# USB_SPI.net
KiCad netlist of a schematic drawn in Altium Designer
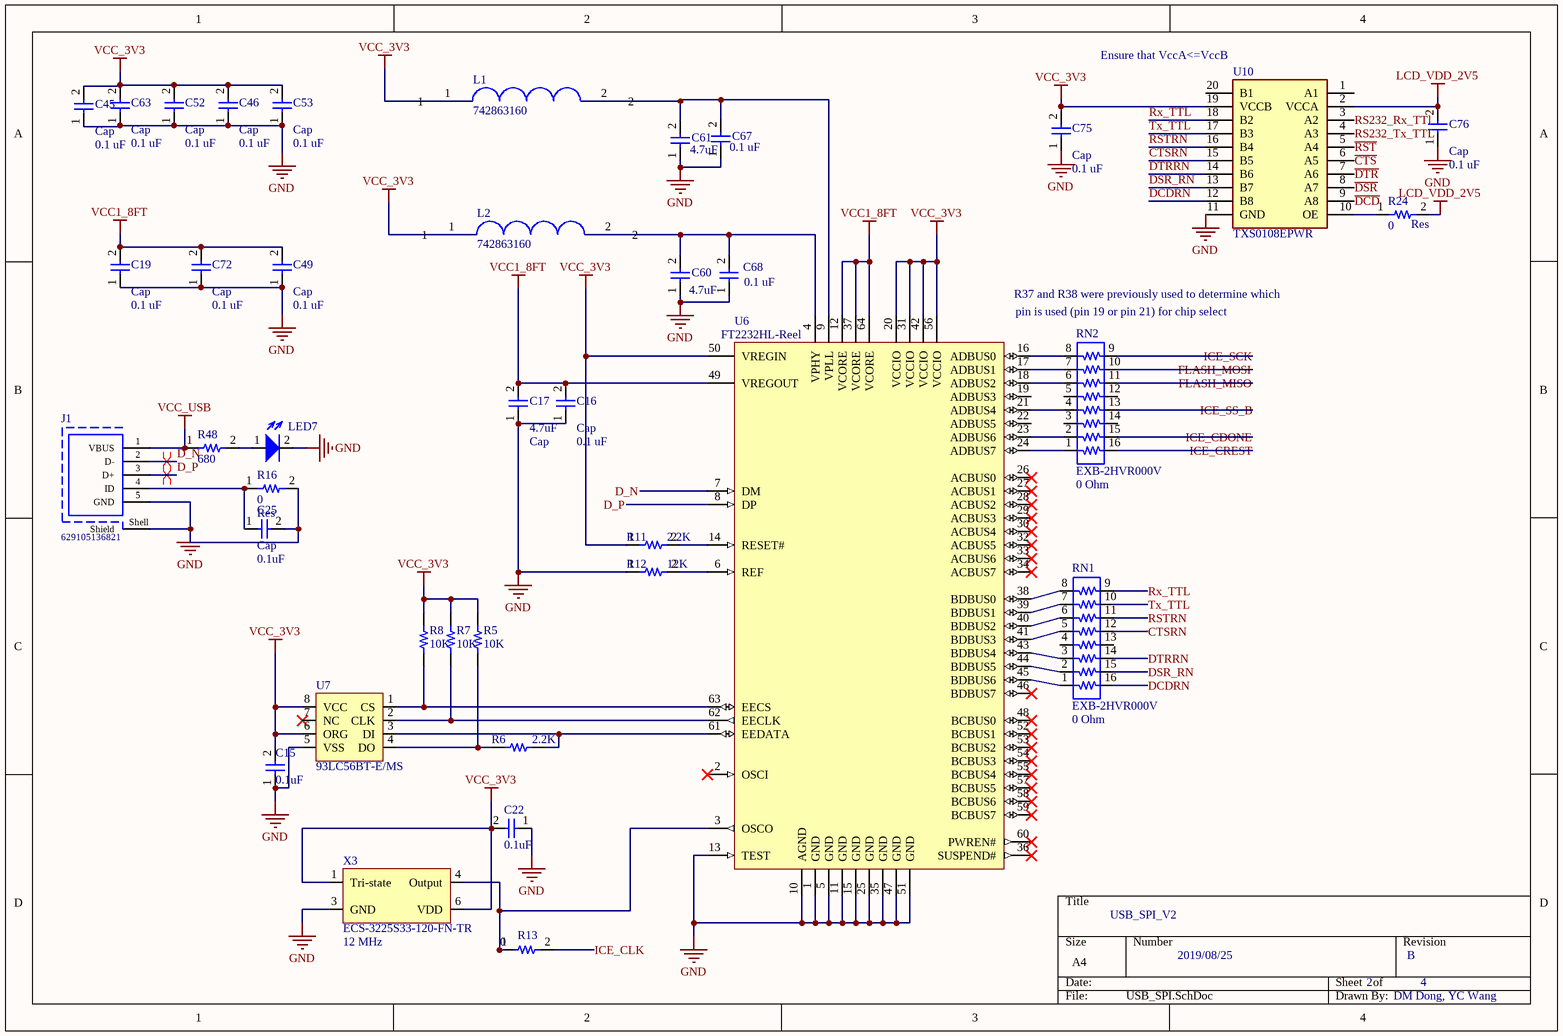
[diagram p0: USB_SPI.SchDoc]

(export (version "E")
  (design (tool "Eeschema 10.0.6"))
  (components
    (comp (ref "C15")
      (value "0.1uF")
      (footprint "Cap_0.1uF")
      (description "Multilayer Ceramic Capacitors MLCC - SMD/SMT 0.1uF 10% 50V AEC-Q200")
      (fields (field (name "Comment") "AC0603KRX7R9BB104") (field (name "CREATED BY") "Daoming Dong"))
      (libsource (lib "USB_FPGA_SLM_v1") (part "Cap_0.1uF"))
    )
    (comp (ref "C16")
      (value "0.1 uF")
      (footprint "Cap_0.1uF_0402")
      (description "Multilayer Ceramic Capacitors MLCC - SMD/SMT 100nF 10V X5R 10%")
      (fields
        (field (name "COMPONENT NAME") "Cap")
        (field (name "Comment") "CC0402KPX5R6BB104")
        (field (name "CREATED BY") "Daoming Dong")
      )
      (libsource (lib "USB_FPGA_SLM_v1") (part "CAP_0.1uF_0402"))
    )
    (comp (ref "C17")
      (value "4.7uF")
      (footprint "CAP_4.7uF_0402")
      (description "Multilayer Ceramic Capacitors MLCC - SMD/SMT 0402 6.3V 4.7uF X5R 10% T: 0.5mm")
      (fields
        (field (name "COMPONENT NAME") "Cap")
        (field (name "Comment") "C1005X5R0J475K050BC")
        (field (name "CREATED BY") "Daoming Dong")
      )
      (libsource (lib "USB_FPGA_SLM_v1") (part "Cap_4.7uF_0402"))
    )
    (comp (ref "C19")
      (value "0.1 uF")
      (footprint "Cap_0.1uF_0402")
      (description "Multilayer Ceramic Capacitors MLCC - SMD/SMT 100nF 10V X5R 10%")
      (fields
        (field (name "COMPONENT NAME") "Cap")
        (field (name "Comment") "CC0402KPX5R6BB104")
        (field (name "CREATED BY") "Daoming Dong")
      )
      (libsource (lib "USB_FPGA_SLM_v1") (part "CAP_0.1uF_0402"))
    )
    (comp (ref "C22")
      (value "0.1uF")
      (footprint "Cap_0.1uF")
      (description "Multilayer Ceramic Capacitors MLCC - SMD/SMT 0.1uF 10% 50V AEC-Q200")
      (fields (field (name "Comment") "AC0603KRX7R9BB104") (field (name "CREATED BY") "Daoming Dong"))
      (libsource (lib "USB_FPGA_SLM_v1") (part "Cap_0.1uF"))
    )
    (comp (ref "C25")
      (value "0.1uF")
      (footprint "Cap_0.1uF")
      (description "Multilayer Ceramic Capacitors MLCC - SMD/SMT 0.1uF 10% 50V AEC-Q200")
      (fields
        (field (name "COMPONENT NAME") "Cap")
        (field (name "Comment") "AC0603KRX7R9BB104")
        (field (name "CREATED BY") "Daoming Dong")
      )
      (libsource (lib "USB_FPGA_SLM_v1") (part "Cap_0.1uF"))
    )
    (comp (ref "C45")
      (value "0.1 uF")
      (footprint "Cap_0.1uF_0402")
      (description "Multilayer Ceramic Capacitors MLCC - SMD/SMT 100nF 10V X5R 10%")
      (fields
        (field (name "COMPONENT NAME") "Cap")
        (field (name "Comment") "CC0402KPX5R6BB104")
        (field (name "CREATED BY") "Daoming Dong")
      )
      (libsource (lib "USB_FPGA_SLM_v1") (part "CAP_0.1uF_0402"))
    )
    (comp (ref "C46")
      (value "0.1 uF")
      (footprint "Cap_0.1uF_0402")
      (description "Multilayer Ceramic Capacitors MLCC - SMD/SMT 100nF 10V X5R 10%")
      (fields
        (field (name "COMPONENT NAME") "Cap")
        (field (name "Comment") "CC0402KPX5R6BB104")
        (field (name "CREATED BY") "Daoming Dong")
      )
      (libsource (lib "USB_FPGA_SLM_v1") (part "CAP_0.1uF_0402"))
    )
    (comp (ref "C49")
      (value "0.1 uF")
      (footprint "Cap_0.1uF_0402")
      (description "Multilayer Ceramic Capacitors MLCC - SMD/SMT 100nF 10V X5R 10%")
      (fields
        (field (name "COMPONENT NAME") "Cap")
        (field (name "Comment") "CC0402KPX5R6BB104")
        (field (name "CREATED BY") "Daoming Dong")
      )
      (libsource (lib "USB_FPGA_SLM_v1") (part "CAP_0.1uF_0402"))
    )
    (comp (ref "C52")
      (value "0.1 uF")
      (footprint "Cap_0.1uF_0402")
      (description "Multilayer Ceramic Capacitors MLCC - SMD/SMT 100nF 10V X5R 10%")
      (fields
        (field (name "COMPONENT NAME") "Cap")
        (field (name "Comment") "CC0402KPX5R6BB104")
        (field (name "CREATED BY") "Daoming Dong")
      )
      (libsource (lib "USB_FPGA_SLM_v1") (part "CAP_0.1uF_0402"))
    )
    (comp (ref "C53")
      (value "0.1 uF")
      (footprint "Cap_0.1uF_0402")
      (description "Multilayer Ceramic Capacitors MLCC - SMD/SMT 100nF 10V X5R 10%")
      (fields
        (field (name "COMPONENT NAME") "Cap")
        (field (name "Comment") "CC0402KPX5R6BB104")
        (field (name "CREATED BY") "Daoming Dong")
      )
      (libsource (lib "USB_FPGA_SLM_v1") (part "CAP_0.1uF_0402"))
    )
    (comp (ref "C60")
      (value "4.7uF")
      (footprint "CAP_4.7uF_0402")
      (description "Multilayer Ceramic Capacitors MLCC - SMD/SMT 0402 6.3V 4.7uF X5R 10% T: 0.5mm")
      (fields (field (name "Comment") "C1005X5R0J475K050BC") (field (name "CREATED BY") "Daoming Dong"))
      (libsource (lib "USB_FPGA_SLM_v1") (part "Cap_4.7uF_0402"))
    )
    (comp (ref "C61")
      (value "4.7uF")
      (footprint "CAP_4.7uF_0402")
      (description "Multilayer Ceramic Capacitors MLCC - SMD/SMT 0402 6.3V 4.7uF X5R 10% T: 0.5mm")
      (fields (field (name "Comment") "C1005X5R0J475K050BC") (field (name "CREATED BY") "Daoming Dong"))
      (libsource (lib "USB_FPGA_SLM_v1") (part "Cap_4.7uF_0402"))
    )
    (comp (ref "C63")
      (value "0.1 uF")
      (footprint "Cap_0.1uF_0402")
      (description "Multilayer Ceramic Capacitors MLCC - SMD/SMT 100nF 10V X5R 10%")
      (fields
        (field (name "COMPONENT NAME") "Cap")
        (field (name "Comment") "CC0402KPX5R6BB104")
        (field (name "CREATED BY") "Daoming Dong")
      )
      (libsource (lib "USB_FPGA_SLM_v1") (part "CAP_0.1uF_0402"))
    )
    (comp (ref "C67")
      (value "0.1 uF")
      (footprint "Cap_0.1uF_0402")
      (description "Multilayer Ceramic Capacitors MLCC - SMD/SMT 100nF 10V X5R 10%")
      (fields (field (name "Comment") "CC0402KPX5R6BB104") (field (name "CREATED BY") "Daoming Dong"))
      (libsource (lib "USB_FPGA_SLM_v1") (part "CAP_0.1uF_0402"))
    )
    (comp (ref "C68")
      (value "0.1 uF")
      (footprint "Cap_0.1uF_0402")
      (description "Multilayer Ceramic Capacitors MLCC - SMD/SMT 100nF 10V X5R 10%")
      (fields (field (name "Comment") "CC0402KPX5R6BB104") (field (name "CREATED BY") "Daoming Dong"))
      (libsource (lib "USB_FPGA_SLM_v1") (part "CAP_0.1uF_0402"))
    )
    (comp (ref "C72")
      (value "0.1 uF")
      (footprint "Cap_0.1uF_0402")
      (description "Multilayer Ceramic Capacitors MLCC - SMD/SMT 100nF 10V X5R 10%")
      (fields
        (field (name "COMPONENT NAME") "Cap")
        (field (name "Comment") "CC0402KPX5R6BB104")
        (field (name "CREATED BY") "Daoming Dong")
      )
      (libsource (lib "USB_FPGA_SLM_v1") (part "CAP_0.1uF_0402"))
    )
    (comp (ref "C75")
      (value "0.1 uF")
      (footprint "Cap_0.1uF_0402")
      (description "Multilayer Ceramic Capacitors MLCC - SMD/SMT 100nF 10V X5R 10%")
      (fields
        (field (name "COMPONENT NAME") "Cap")
        (field (name "Comment") "CC0402KPX5R6BB104")
        (field (name "CREATED BY") "Daoming Dong")
      )
      (libsource (lib "USB_FPGA_SLM_v1") (part "CAP_0.1uF_0402"))
    )
    (comp (ref "C76")
      (value "0.1 uF")
      (footprint "Cap_0.1uF_0402")
      (description "Multilayer Ceramic Capacitors MLCC - SMD/SMT 100nF 10V X5R 10%")
      (fields
        (field (name "COMPONENT NAME") "Cap")
        (field (name "Comment") "CC0402KPX5R6BB104")
        (field (name "CREATED BY") "Daoming Dong")
      )
      (libsource (lib "USB_FPGA_SLM_v1") (part "CAP_0.1uF_0402"))
    )
    (comp (ref "J1")
      (value "629105136821")
      (footprint "629105136821")
      (description "Micro USB 2.0 Type B Receptacle WR-COM, Horizontal, SMT, with Pads and Pegs")
      (fields (field (name "PUBLISHER") "Wurth Elektronik"))
      (libsource (lib "Altium_WR-COM_USB-Connectors (rev18d)") (part "629105136821"))
    )
    (comp (ref "L1")
      (value "742863160")
      (footprint "FerriteBeads")
      (description "Ferrite Bead, 0603 [1608 Metric], 600 ohm, 500 mA, WE-CBF HF Series, 0.35 ohm, ± 25%")
      (fields (field (name "CREATED BY") "Youchao Wang"))
      (libsource (lib "USB_FPGA_SLM_v1") (part "Ferrite Bead"))
    )
    (comp (ref "L2")
      (value "742863160")
      (footprint "FerriteBeads")
      (description "Ferrite Bead, 0603 [1608 Metric], 600 ohm, 500 mA, WE-CBF HF Series, 0.35 ohm, ± 25%")
      (fields (field (name "CREATED BY") "Youchao Wang"))
      (libsource (lib "USB_FPGA_SLM_v1") (part "Ferrite Bead"))
    )
    (comp (ref "LED7")
      (value "TLMS1000-GS08")
      (footprint "LED_RED")
      (description "Standard LEDs - SMD RED")
      (fields (field (name "CREATED BY") "Daoming Dong"))
      (libsource (lib "USB_FPGA_SLM_v1") (part "LED_RED"))
    )
    (comp (ref "R5")
      (value "10K")
      (footprint "RES_10K")
      (description "Thin Film Resistors - SMD 10K ohm 0.05% 50 ppm High-Precision")
      (fields (field (name "Comment") "RT0603WRE0710KL") (field (name "CREATED BY") "Daoming Dong"))
      (libsource (lib "USB_FPGA_SLM_v1") (part "Res_10K"))
    )
    (comp (ref "R6")
      (value "2.2K")
      (footprint "RES_2.2K")
      (description "Thick Film Resistors - SMD 1/10Watt 2.2Kohms 5% Commercial Use")
      (fields (field (name "Comment") "CRCW06032K20JNEAC") (field (name "CREATED BY") "Daoming Dong"))
      (libsource (lib "USB_FPGA_SLM_v1") (part "Res_2.2K"))
    )
    (comp (ref "R7")
      (value "10K")
      (footprint "RES_10K")
      (description "Thin Film Resistors - SMD 10K ohm 0.05% 50 ppm High-Precision")
      (fields (field (name "Comment") "RT0603WRE0710KL") (field (name "CREATED BY") "Daoming Dong"))
      (libsource (lib "USB_FPGA_SLM_v1") (part "Res_10K"))
    )
    (comp (ref "R8")
      (value "10K")
      (footprint "RES_10K")
      (description "Thin Film Resistors - SMD 10K ohm 0.05% 50 ppm High-Precision")
      (fields (field (name "Comment") "RT0603WRE0710KL") (field (name "CREATED BY") "Daoming Dong"))
      (libsource (lib "USB_FPGA_SLM_v1") (part "Res_10K"))
    )
    (comp (ref "R11")
      (value "2.2K")
      (footprint "RES_2.2K")
      (description "Thick Film Resistors - SMD 1/10Watt 2.2Kohms 5% Commercial Use")
      (fields (field (name "Comment") "CRCW06032K20JNEAC") (field (name "CREATED BY") "Daoming Dong"))
      (libsource (lib "") (part "Res_2.2K_1"))
    )
    (comp (ref "R12")
      (value "12K")
      (footprint "RES_12K")
      (description "Thick Film Resistors - SMD 12K ohm 1% 1/10W AEC-Q200")
      (fields (field (name "Comment") "AC0603FR-1012KL") (field (name "CREATED BY") "Daoming Dong"))
      (libsource (lib "USB_FPGA_SLM_v1") (part "Res_12K"))
    )
    (comp (ref "R13")
      (value "0")
      (footprint "RES_0")
      (description "Thick Film Resistors - SMD 1/10Watt 0ohms Commercial Use")
      (fields (field (name "Comment") "CRCW06030000Z0EAC") (field (name "CREATED BY") "Daoming Dong"))
      (libsource (lib "USB_FPGA_SLM_v1") (part "Res_0"))
    )
    (comp (ref "R16")
      (value "0")
      (footprint "RES_0")
      (description "Thick Film Resistors - SMD 1/10Watt 0ohms Commercial Use")
      (fields
        (field (name "COMPONENT NAME") "Res")
        (field (name "Comment") "CRCW06030000Z0EAC")
        (field (name "CREATED BY") "Daoming Dong")
      )
      (libsource (lib "USB_FPGA_SLM_v1") (part "Res_0"))
    )
    (comp (ref "R24")
      (value "0")
      (footprint "RES_0")
      (description "Thick Film Resistors - SMD 1/10Watt 0ohms Commercial Use")
      (fields
        (field (name "COMPONENT NAME") "Res")
        (field (name "Comment") "CRCW06030000Z0EAC")
        (field (name "CREATED BY") "Daoming Dong")
      )
      (libsource (lib "USB_FPGA_SLM_v1") (part "Res_0"))
    )
    (comp (ref "R48")
      (value "680")
      (footprint "RES_680")
      (description "Thin Film Resistors - SMD 680 ohm 1% 50 ppm Thin Film")
      (fields (field (name "Comment") "RT0603FRE13680RL") (field (name "CREATED BY") "Daoming Dong"))
      (libsource (lib "USB_FPGA_SLM_v1") (part "Res_680"))
    )
    (comp (ref "RN1")
      (value "EXB-2HVR000V")
      (footprint "ResArray_0")
      (description "Resistor Networks & Arrays 0402 Zero ohm Jumper Convex Term AEC-Q200")
      (fields (field (name "ALTIUM_VALUE") "0 Ohm") (field (name "CREATED BY") "Daoming Dong"))
      (libsource (lib "USB_FPGA_SLM_v1") (part "ResArray_0"))
    )
    (comp (ref "RN2")
      (value "EXB-2HVR000V")
      (footprint "ResArray_0")
      (description "Resistor Networks & Arrays 0402 Zero ohm Jumper Convex Term AEC-Q200")
      (fields (field (name "ALTIUM_VALUE") "0 Ohm") (field (name "CREATED BY") "Daoming Dong"))
      (libsource (lib "USB_FPGA_SLM_v1") (part "ResArray_0"))
    )
    (comp (ref "U6")
      (value "FT2232HL-Reel")
      (footprint "LQFP-64_N")
      (description "Dual High Speed USB To Multipurpose UART/FIFO IC, 64-pin LQFP, Tape and Reel")
      (fields (field (name "MANUFACTURER") "FTDI"))
      (libsource (lib "FTDI FT Series") (part "FT2232HL-Reel"))
    )
    (comp (ref "U7")
      (value "93LC56BT-E/MS")
      (footprint "EEPROM")
      (description "EEPROM 128x16 for FT2232")
      (fields (field (name "CREATED BY") "Daoming Dong"))
      (libsource (lib "USB_FPGA_SLM_v1") (part "EEPROM"))
    )
    (comp (ref "U10")
      (value "TXS0108EPWR")
      (footprint "SOP65P640X120-20N")
      (description "Integrated Circuit")
      (fields (field (name "MOUSER PART NUMBER") "595-TXS0108EPWR"))
      (libsource (lib "USB_FPGA_SLM_v1") (part "Level_Shfter_8bits"))
    )
    (comp (ref "X3")
      (value "ECS-3225S33-120-FN-TR")
      (footprint "12MHzOscillator")
      (description "Standard Clock Oscillators 12MHz 3.3V 10ppm -40C +85C")
      (fields (field (name "ALTIUM_VALUE") "12 MHz"))
      (libsource (lib "USB_FPGA_SLM_v1") (part "12MHzOscillator"))
    )
  )
  (nets
    (net (code "1") (name "/CTSRN") (class "Default")
      (node (ref "RN1") (pin "12") (pinfunction "12_12") (pintype "passive"))
      (node (ref "U10") (pin "15") (pinfunction "B5_15") (pintype "passive"))
    )
    (net (code "2") (name "/DCDRN") (class "Default")
      (node (ref "RN1") (pin "16") (pinfunction "16_16") (pintype "passive"))
      (node (ref "U10") (pin "12") (pinfunction "B8_12") (pintype "passive"))
    )
    (net (code "3") (name "/DSR_RN") (class "Default")
      (node (ref "RN1") (pin "15") (pinfunction "15_15") (pintype "passive"))
      (node (ref "U10") (pin "13") (pinfunction "B7_13") (pintype "passive"))
    )
    (net (code "4") (name "/DTRRN") (class "Default")
      (node (ref "RN1") (pin "14") (pinfunction "14_14") (pintype "passive"))
      (node (ref "U10") (pin "14") (pinfunction "B6_14") (pintype "passive"))
    )
    (net (code "5") (name "/D_N") (class "Default")
      (node (ref "J1") (pin "2") (pinfunction "D-_2") (pintype "passive"))
      (node (ref "U6") (pin "7") (pinfunction "DM_7") (pintype "input"))
    )
    (net (code "6") (name "/D_P") (class "Default")
      (node (ref "J1") (pin "3") (pinfunction "D+_3") (pintype "passive"))
      (node (ref "U6") (pin "8") (pinfunction "DP_8") (pintype "input"))
    )
    (net (code "7") (name "/FLASH_MISO") (class "Default")
      (node (ref "RN2") (pin "11") (pinfunction "11_11") (pintype "passive"))
    )
    (net (code "8") (name "/FLASH_MOSI") (class "Default")
      (node (ref "RN2") (pin "10") (pinfunction "10_10") (pintype "passive"))
    )
    (net (code "9") (name "/ICE_CDONE") (class "Default")
      (node (ref "RN2") (pin "15") (pinfunction "15_15") (pintype "passive"))
    )
    (net (code "10") (name "/ICE_CLK") (class "Default")
      (node (ref "R13") (pin "2") (pinfunction "2_2") (pintype "passive"))
    )
    (net (code "11") (name "/ICE_CREST") (class "Default")
      (node (ref "RN2") (pin "16") (pinfunction "16_16") (pintype "passive"))
    )
    (net (code "12") (name "/ICE_SCK") (class "Default")
      (node (ref "RN2") (pin "9") (pinfunction "9_9") (pintype "passive"))
    )
    (net (code "13") (name "/ICE_SS_B") (class "Default")
      (node (ref "RN2") (pin "13") (pinfunction "13_13") (pintype "passive"))
    )
    (net (code "14") (name "/RS232_Rx_TTl") (class "Default")
      (node (ref "U10") (pin "3") (pinfunction "A2_3") (pintype "passive"))
    )
    (net (code "15") (name "/RS232_Tx_TTL") (class "Default")
      (node (ref "U10") (pin "4") (pinfunction "A3_4") (pintype "passive"))
    )
    (net (code "16") (name "/RSTRN") (class "Default")
      (node (ref "RN1") (pin "11") (pinfunction "11_11") (pintype "passive"))
      (node (ref "U10") (pin "16") (pinfunction "B4_16") (pintype "passive"))
    )
    (net (code "17") (name "/Rx_TTL") (class "Default")
      (node (ref "RN1") (pin "9") (pinfunction "9_9") (pintype "passive"))
      (node (ref "U10") (pin "18") (pinfunction "B2_18") (pintype "passive"))
    )
    (net (code "18") (name "/Tx_TTL") (class "Default")
      (node (ref "RN1") (pin "10") (pinfunction "10_10") (pintype "passive"))
      (node (ref "U10") (pin "17") (pinfunction "B3_17") (pintype "passive"))
    )
    (net (code "19") (name "/~{CTS}") (class "Default")
      (node (ref "U10") (pin "6") (pinfunction "A5_6") (pintype "passive"))
    )
    (net (code "20") (name "/~{DCD}") (class "Default")
      (node (ref "U10") (pin "9") (pinfunction "A8_9") (pintype "passive"))
    )
    (net (code "21") (name "/~{DSR}") (class "Default")
      (node (ref "U10") (pin "8") (pinfunction "A7_8") (pintype "passive"))
    )
    (net (code "22") (name "/~{DTR}") (class "Default")
      (node (ref "U10") (pin "7") (pinfunction "A6_7") (pintype "passive"))
    )
    (net (code "23") (name "/~{RST}") (class "Default")
      (node (ref "U10") (pin "5") (pinfunction "A4_5") (pintype "passive"))
    )
    (net (code "24") (name "GND") (class "Default")
      (node (ref "C15") (pin "1") (pinfunction "1_1") (pintype "passive"))
      (node (ref "C16") (pin "1") (pinfunction "1_1") (pintype "passive"))
      (node (ref "C17") (pin "1") (pinfunction "1_1") (pintype "passive"))
      (node (ref "C19") (pin "1") (pinfunction "1_1") (pintype "passive"))
      (node (ref "C22") (pin "1") (pinfunction "1_1") (pintype "passive"))
      (node (ref "C25") (pin "2") (pinfunction "2_2") (pintype "passive"))
      (node (ref "C45") (pin "1") (pinfunction "1_1") (pintype "passive"))
      (node (ref "C46") (pin "1") (pinfunction "1_1") (pintype "passive"))
      (node (ref "C49") (pin "1") (pinfunction "1_1") (pintype "passive"))
      (node (ref "C52") (pin "1") (pinfunction "1_1") (pintype "passive"))
      (node (ref "C53") (pin "1") (pinfunction "1_1") (pintype "passive"))
      (node (ref "C60") (pin "1") (pinfunction "1_1") (pintype "passive"))
      (node (ref "C61") (pin "1") (pinfunction "1_1") (pintype "passive"))
      (node (ref "C63") (pin "1") (pinfunction "1_1") (pintype "passive"))
      (node (ref "C67") (pin "1") (pinfunction "1_1") (pintype "passive"))
      (node (ref "C68") (pin "1") (pinfunction "1_1") (pintype "passive"))
      (node (ref "C72") (pin "1") (pinfunction "1_1") (pintype "passive"))
      (node (ref "C75") (pin "1") (pinfunction "1_1") (pintype "passive"))
      (node (ref "C76") (pin "1") (pinfunction "1_1") (pintype "passive"))
      (node (ref "J1") (pin "5") (pinfunction "GND_5") (pintype "passive"))
      (node (ref "J1") (pin "Shell") (pinfunction "Shield_Shell") (pintype "passive"))
      (node (ref "LED7") (pin "2") (pinfunction "Cathode_2") (pintype "passive"))
      (node (ref "R12") (pin "1") (pinfunction "1_1") (pintype "passive"))
      (node (ref "R16") (pin "2") (pinfunction "2_2") (pintype "passive"))
      (node (ref "U10") (pin "11") (pinfunction "GND_11") (pintype "passive"))
      (node (ref "U6") (pin "1") (pinfunction "GND_1") (pintype "power_in"))
      (node (ref "U6") (pin "10") (pinfunction "AGND_10") (pintype "power_in"))
      (node (ref "U6") (pin "11") (pinfunction "GND_11") (pintype "power_in"))
      (node (ref "U6") (pin "13") (pinfunction "TEST_13") (pintype "input"))
      (node (ref "U6") (pin "15") (pinfunction "GND_15") (pintype "power_in"))
      (node (ref "U6") (pin "25") (pinfunction "GND_25") (pintype "power_in"))
      (node (ref "U6") (pin "35") (pinfunction "GND_35") (pintype "power_in"))
      (node (ref "U6") (pin "47") (pinfunction "GND_47") (pintype "power_in"))
      (node (ref "U6") (pin "5") (pinfunction "GND_5") (pintype "power_in"))
      (node (ref "U6") (pin "51") (pinfunction "GND_51") (pintype "power_in"))
      (node (ref "U7") (pin "5") (pinfunction "VSS_5") (pintype "passive"))
      (node (ref "X3") (pin "3") (pinfunction "GND_3") (pintype "passive"))
    )
    (net (code "25") (name "LCD_VDD_2V5") (class "Default")
      (node (ref "C76") (pin "2") (pinfunction "2_2") (pintype "passive"))
      (node (ref "R24") (pin "2") (pinfunction "2_2") (pintype "passive"))
      (node (ref "U10") (pin "2") (pinfunction "VCCA_2") (pintype "passive"))
    )
    (net (code "26") (name "Net-(J1-ID)") (class "Default")
      (node (ref "C25") (pin "1") (pinfunction "1_1") (pintype "passive"))
      (node (ref "J1") (pin "4") (pinfunction "ID_4") (pintype "passive"))
      (node (ref "R16") (pin "1") (pinfunction "1_1") (pintype "passive"))
    )
    (net (code "27") (name "Net-(LED7-Anode)") (class "Default")
      (node (ref "LED7") (pin "1") (pinfunction "Anode_1") (pintype "passive"))
      (node (ref "R48") (pin "2") (pinfunction "2_2") (pintype "passive"))
    )
    (net (code "28") (name "Net-(U6-ADBUS0)") (class "Default")
      (node (ref "RN2") (pin "8") (pinfunction "8_8") (pintype "passive"))
      (node (ref "U6") (pin "16") (pinfunction "ADBUS0_16") (pintype "bidirectional"))
    )
    (net (code "29") (name "Net-(U6-ADBUS1)") (class "Default")
      (node (ref "RN2") (pin "7") (pinfunction "7_7") (pintype "passive"))
      (node (ref "U6") (pin "17") (pinfunction "ADBUS1_17") (pintype "bidirectional"))
    )
    (net (code "30") (name "Net-(U6-ADBUS2)") (class "Default")
      (node (ref "RN2") (pin "6") (pinfunction "6_6") (pintype "passive"))
      (node (ref "U6") (pin "18") (pinfunction "ADBUS2_18") (pintype "bidirectional"))
    )
    (net (code "31") (name "Net-(U6-ADBUS4)") (class "Default")
      (node (ref "RN2") (pin "4") (pinfunction "4_4") (pintype "passive"))
      (node (ref "U6") (pin "21") (pinfunction "ADBUS4_21") (pintype "bidirectional"))
    )
    (net (code "32") (name "Net-(U6-ADBUS6)") (class "Default")
      (node (ref "RN2") (pin "2") (pinfunction "2_2") (pintype "passive"))
      (node (ref "U6") (pin "23") (pinfunction "ADBUS6_23") (pintype "bidirectional"))
    )
    (net (code "33") (name "Net-(U6-ADBUS7)") (class "Default")
      (node (ref "RN2") (pin "1") (pinfunction "1_1") (pintype "passive"))
      (node (ref "U6") (pin "24") (pinfunction "ADBUS7_24") (pintype "bidirectional"))
    )
    (net (code "34") (name "Net-(U6-BDBUS0)") (class "Default")
      (node (ref "RN1") (pin "8") (pinfunction "8_8") (pintype "passive"))
      (node (ref "U6") (pin "38") (pinfunction "BDBUS0_38") (pintype "bidirectional"))
    )
    (net (code "35") (name "Net-(U6-BDBUS1)") (class "Default")
      (node (ref "RN1") (pin "7") (pinfunction "7_7") (pintype "passive"))
      (node (ref "U6") (pin "39") (pinfunction "BDBUS1_39") (pintype "bidirectional"))
    )
    (net (code "36") (name "Net-(U6-BDBUS2)") (class "Default")
      (node (ref "RN1") (pin "6") (pinfunction "6_6") (pintype "passive"))
      (node (ref "U6") (pin "40") (pinfunction "BDBUS2_40") (pintype "bidirectional"))
    )
    (net (code "37") (name "Net-(U6-BDBUS3)") (class "Default")
      (node (ref "RN1") (pin "5") (pinfunction "5_5") (pintype "passive"))
      (node (ref "U6") (pin "41") (pinfunction "BDBUS3_41") (pintype "bidirectional"))
    )
    (net (code "38") (name "Net-(U6-BDBUS4)") (class "Default")
      (node (ref "RN1") (pin "3") (pinfunction "3_3") (pintype "passive"))
      (node (ref "U6") (pin "43") (pinfunction "BDBUS4_43") (pintype "bidirectional"))
    )
    (net (code "39") (name "Net-(U6-BDBUS5)") (class "Default")
      (node (ref "RN1") (pin "2") (pinfunction "2_2") (pintype "passive"))
      (node (ref "U6") (pin "44") (pinfunction "BDBUS5_44") (pintype "bidirectional"))
    )
    (net (code "40") (name "Net-(U6-BDBUS6)") (class "Default")
      (node (ref "RN1") (pin "1") (pinfunction "1_1") (pintype "passive"))
      (node (ref "U6") (pin "45") (pinfunction "BDBUS6_45") (pintype "bidirectional"))
    )
    (net (code "41") (name "Net-(U6-EECLK)") (class "Default")
      (node (ref "R7") (pin "1") (pinfunction "1_1") (pintype "passive"))
      (node (ref "U6") (pin "62") (pinfunction "EECLK_62") (pintype "output"))
      (node (ref "U7") (pin "2") (pinfunction "CLK_2") (pintype "passive"))
    )
    (net (code "42") (name "Net-(U6-EECS)") (class "Default")
      (node (ref "R8") (pin "1") (pinfunction "1_1") (pintype "passive"))
      (node (ref "U6") (pin "63") (pinfunction "EECS_63") (pintype "bidirectional"))
      (node (ref "U7") (pin "1") (pinfunction "CS_1") (pintype "passive"))
    )
    (net (code "43") (name "Net-(U6-EEDATA)") (class "Default")
      (node (ref "R6") (pin "2") (pinfunction "2_2") (pintype "passive"))
      (node (ref "U6") (pin "61") (pinfunction "EEDATA_61") (pintype "bidirectional"))
      (node (ref "U7") (pin "3") (pinfunction "DI_3") (pintype "passive"))
    )
    (net (code "44") (name "Net-(U6-OSCO)") (class "Default")
      (node (ref "R13") (pin "1") (pinfunction "1_1") (pintype "passive"))
      (node (ref "U6") (pin "3") (pinfunction "OSCO_3") (pintype "output"))
      (node (ref "X3") (pin "4") (pinfunction "Output_4") (pintype "passive"))
    )
    (net (code "45") (name "Net-(U6-REF)") (class "Default")
      (node (ref "R12") (pin "2") (pinfunction "2_2") (pintype "passive"))
      (node (ref "U6") (pin "6") (pinfunction "REF_6") (pintype "input"))
    )
    (net (code "46") (name "Net-(U6-RESET#)") (class "Default")
      (node (ref "R11") (pin "2") (pinfunction "2_2") (pintype "passive"))
      (node (ref "U6") (pin "14") (pinfunction "RESET#_14") (pintype "input"))
    )
    (net (code "47") (name "Net-(U6-VPHY)") (class "Default")
      (node (ref "C60") (pin "2") (pinfunction "2_2") (pintype "passive"))
      (node (ref "C68") (pin "2") (pinfunction "2_2") (pintype "passive"))
      (node (ref "L2") (pin "2") (pinfunction "2_2") (pintype "passive"))
      (node (ref "U6") (pin "4") (pinfunction "VPHY_4") (pintype "power_in"))
    )
    (net (code "48") (name "Net-(U6-VPLL)") (class "Default")
      (node (ref "C61") (pin "2") (pinfunction "2_2") (pintype "passive"))
      (node (ref "C67") (pin "2") (pinfunction "2_2") (pintype "passive"))
      (node (ref "L1") (pin "2") (pinfunction "2_2") (pintype "passive"))
      (node (ref "U6") (pin "9") (pinfunction "VPLL_9") (pintype "power_in"))
    )
    (net (code "49") (name "Net-(U7-DO)") (class "Default")
      (node (ref "R5") (pin "1") (pinfunction "1_1") (pintype "passive"))
      (node (ref "R6") (pin "1") (pinfunction "1_1") (pintype "passive"))
      (node (ref "U7") (pin "4") (pinfunction "DO_4") (pintype "passive"))
    )
    (net (code "50") (name "Net-(U10-OE)") (class "Default")
      (node (ref "R24") (pin "1") (pinfunction "1_1") (pintype "passive"))
      (node (ref "U10") (pin "10") (pinfunction "OE_10") (pintype "passive"))
    )
    (net (code "51") (name "VCC1_8FT") (class "Default")
      (node (ref "C16") (pin "2") (pinfunction "2_2") (pintype "passive"))
      (node (ref "C17") (pin "2") (pinfunction "2_2") (pintype "passive"))
      (node (ref "C19") (pin "2") (pinfunction "2_2") (pintype "passive"))
      (node (ref "C49") (pin "2") (pinfunction "2_2") (pintype "passive"))
      (node (ref "C72") (pin "2") (pinfunction "2_2") (pintype "passive"))
      (node (ref "U6") (pin "12") (pinfunction "VCORE_12") (pintype "power_in"))
      (node (ref "U6") (pin "37") (pinfunction "VCORE_37") (pintype "power_in"))
      (node (ref "U6") (pin "49") (pinfunction "VREGOUT_49") (pintype "power_in"))
      (node (ref "U6") (pin "64") (pinfunction "VCORE_64") (pintype "power_in"))
    )
    (net (code "52") (name "VCC_3V3") (class "Default")
      (node (ref "C15") (pin "2") (pinfunction "2_2") (pintype "passive"))
      (node (ref "C22") (pin "2") (pinfunction "2_2") (pintype "passive"))
      (node (ref "C45") (pin "2") (pinfunction "2_2") (pintype "passive"))
      (node (ref "C46") (pin "2") (pinfunction "2_2") (pintype "passive"))
      (node (ref "C52") (pin "2") (pinfunction "2_2") (pintype "passive"))
      (node (ref "C53") (pin "2") (pinfunction "2_2") (pintype "passive"))
      (node (ref "C63") (pin "2") (pinfunction "2_2") (pintype "passive"))
      (node (ref "C75") (pin "2") (pinfunction "2_2") (pintype "passive"))
      (node (ref "L1") (pin "1") (pinfunction "1_1") (pintype "passive"))
      (node (ref "L2") (pin "1") (pinfunction "1_1") (pintype "passive"))
      (node (ref "R11") (pin "1") (pinfunction "1_1") (pintype "passive"))
      (node (ref "R5") (pin "2") (pinfunction "2_2") (pintype "passive"))
      (node (ref "R7") (pin "2") (pinfunction "2_2") (pintype "passive"))
      (node (ref "R8") (pin "2") (pinfunction "2_2") (pintype "passive"))
      (node (ref "U10") (pin "19") (pinfunction "VCCB_19") (pintype "passive"))
      (node (ref "U6") (pin "20") (pinfunction "VCCIO_20") (pintype "power_in"))
      (node (ref "U6") (pin "31") (pinfunction "VCCIO_31") (pintype "power_in"))
      (node (ref "U6") (pin "42") (pinfunction "VCCIO_42") (pintype "power_in"))
      (node (ref "U6") (pin "50") (pinfunction "VREGIN_50") (pintype "power_in"))
      (node (ref "U6") (pin "56") (pinfunction "VCCIO_56") (pintype "power_in"))
      (node (ref "U7") (pin "6") (pinfunction "ORG_6") (pintype "passive"))
      (node (ref "U7") (pin "8") (pinfunction "VCC_8") (pintype "passive"))
      (node (ref "X3") (pin "1") (pinfunction "Tri-state_1") (pintype "passive"))
      (node (ref "X3") (pin "6") (pinfunction "VDD_6") (pintype "passive"))
    )
    (net (code "53") (name "VCC_USB") (class "Default")
      (node (ref "J1") (pin "1") (pinfunction "VBUS_1") (pintype "passive"))
      (node (ref "R48") (pin "1") (pinfunction "1_1") (pintype "passive"))
    )
    (net (code "54") (name "unconnected-(RN1-Pad4)") (class "Default")
      (node (ref "RN1") (pin "4") (pinfunction "4_4") (pintype "passive"))
    )
    (net (code "55") (name "unconnected-(RN1-Pad13)") (class "Default")
      (node (ref "RN1") (pin "13") (pinfunction "13_13") (pintype "passive"))
    )
    (net (code "56") (name "unconnected-(RN2-Pad3)") (class "Default")
      (node (ref "RN2") (pin "3") (pinfunction "3_3") (pintype "passive"))
    )
    (net (code "57") (name "unconnected-(RN2-Pad5)") (class "Default")
      (node (ref "RN2") (pin "5") (pinfunction "5_5") (pintype "passive"))
    )
    (net (code "58") (name "unconnected-(RN2-Pad12)") (class "Default")
      (node (ref "RN2") (pin "12") (pinfunction "12_12") (pintype "passive"))
    )
    (net (code "59") (name "unconnected-(RN2-Pad14)") (class "Default")
      (node (ref "RN2") (pin "14") (pinfunction "14_14") (pintype "passive"))
    )
    (net (code "60") (name "unconnected-(U6-ACBUS0-Pad26)") (class "Default")
      (node (ref "U6") (pin "26") (pinfunction "ACBUS0_26") (pintype "bidirectional+no_connect"))
    )
    (net (code "61") (name "unconnected-(U6-ACBUS1-Pad27)") (class "Default")
      (node (ref "U6") (pin "27") (pinfunction "ACBUS1_27") (pintype "bidirectional+no_connect"))
    )
    (net (code "62") (name "unconnected-(U6-ACBUS2-Pad28)") (class "Default")
      (node (ref "U6") (pin "28") (pinfunction "ACBUS2_28") (pintype "bidirectional+no_connect"))
    )
    (net (code "63") (name "unconnected-(U6-ACBUS3-Pad29)") (class "Default")
      (node (ref "U6") (pin "29") (pinfunction "ACBUS3_29") (pintype "bidirectional+no_connect"))
    )
    (net (code "64") (name "unconnected-(U6-ACBUS4-Pad30)") (class "Default")
      (node (ref "U6") (pin "30") (pinfunction "ACBUS4_30") (pintype "bidirectional+no_connect"))
    )
    (net (code "65") (name "unconnected-(U6-ACBUS5-Pad32)") (class "Default")
      (node (ref "U6") (pin "32") (pinfunction "ACBUS5_32") (pintype "bidirectional+no_connect"))
    )
    (net (code "66") (name "unconnected-(U6-ACBUS6-Pad33)") (class "Default")
      (node (ref "U6") (pin "33") (pinfunction "ACBUS6_33") (pintype "bidirectional+no_connect"))
    )
    (net (code "67") (name "unconnected-(U6-ACBUS7-Pad34)") (class "Default")
      (node (ref "U6") (pin "34") (pinfunction "ACBUS7_34") (pintype "bidirectional+no_connect"))
    )
    (net (code "68") (name "unconnected-(U6-ADBUS3-Pad19)") (class "Default")
      (node (ref "U6") (pin "19") (pinfunction "ADBUS3_19") (pintype "bidirectional"))
    )
    (net (code "69") (name "unconnected-(U6-ADBUS5-Pad22)") (class "Default")
      (node (ref "U6") (pin "22") (pinfunction "ADBUS5_22") (pintype "bidirectional"))
    )
    (net (code "70") (name "unconnected-(U6-BCBUS0-Pad48)") (class "Default")
      (node (ref "U6") (pin "48") (pinfunction "BCBUS0_48") (pintype "bidirectional+no_connect"))
    )
    (net (code "71") (name "unconnected-(U6-BCBUS1-Pad52)") (class "Default")
      (node (ref "U6") (pin "52") (pinfunction "BCBUS1_52") (pintype "bidirectional+no_connect"))
    )
    (net (code "72") (name "unconnected-(U6-BCBUS2-Pad53)") (class "Default")
      (node (ref "U6") (pin "53") (pinfunction "BCBUS2_53") (pintype "bidirectional+no_connect"))
    )
    (net (code "73") (name "unconnected-(U6-BCBUS3-Pad54)") (class "Default")
      (node (ref "U6") (pin "54") (pinfunction "BCBUS3_54") (pintype "bidirectional+no_connect"))
    )
    (net (code "74") (name "unconnected-(U6-BCBUS4-Pad55)") (class "Default")
      (node (ref "U6") (pin "55") (pinfunction "BCBUS4_55") (pintype "bidirectional+no_connect"))
    )
    (net (code "75") (name "unconnected-(U6-BCBUS5-Pad57)") (class "Default")
      (node (ref "U6") (pin "57") (pinfunction "BCBUS5_57") (pintype "bidirectional+no_connect"))
    )
    (net (code "76") (name "unconnected-(U6-BCBUS6-Pad58)") (class "Default")
      (node (ref "U6") (pin "58") (pinfunction "BCBUS6_58") (pintype "bidirectional+no_connect"))
    )
    (net (code "77") (name "unconnected-(U6-BCBUS7-Pad59)") (class "Default")
      (node (ref "U6") (pin "59") (pinfunction "BCBUS7_59") (pintype "bidirectional+no_connect"))
    )
    (net (code "78") (name "unconnected-(U6-BDBUS7-Pad46)") (class "Default")
      (node (ref "U6") (pin "46") (pinfunction "BDBUS7_46") (pintype "bidirectional+no_connect"))
    )
    (net (code "79") (name "unconnected-(U6-OSCI-Pad2)") (class "Default")
      (node (ref "U6") (pin "2") (pinfunction "OSCI_2") (pintype "input+no_connect"))
    )
    (net (code "80") (name "unconnected-(U6-PWREN#-Pad60)") (class "Default")
      (node (ref "U6") (pin "60") (pinfunction "PWREN#_60") (pintype "output+no_connect"))
    )
    (net (code "81") (name "unconnected-(U6-SUSPEND#-Pad36)") (class "Default")
      (node (ref "U6") (pin "36") (pinfunction "SUSPEND#_36") (pintype "output+no_connect"))
    )
    (net (code "82") (name "unconnected-(U7-NC-Pad7)") (class "Default")
      (node (ref "U7") (pin "7") (pinfunction "NC_7") (pintype "passive+no_connect"))
    )
    (net (code "83") (name "unconnected-(U10-A1-Pad1)") (class "Default")
      (node (ref "U10") (pin "1") (pinfunction "A1_1") (pintype "passive"))
    )
    (net (code "84") (name "unconnected-(U10-B1-Pad20)") (class "Default")
      (node (ref "U10") (pin "20") (pinfunction "B1_20") (pintype "passive"))
    )
  )
)
